# Teste_lad.net
KiCad netlist of a schematic drawn in EAGLE
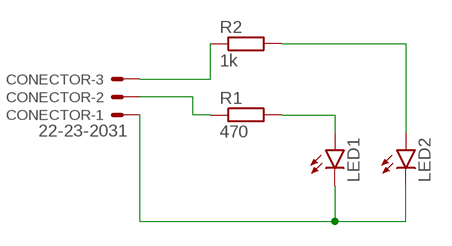
[diagram p0: schematic, sheet 1]

(export (version "E")
  (design (tool "Eeschema 10.0.6"))
  (components
    (comp (ref "CONECTOR")
      (value "22-23-2031")
      (footprint "eagle-import:22-23-2031")
      (fields (field (name "MF") "MOLEX"))
      (libsource (lib "eagle-import") (part "22-23-2031"))
    )
    (comp (ref "LED1")
      (value "LED5MM")
      (footprint "eagle-import:LED5MM")
      (libsource (lib "eagle-import") (part "LED5MM"))
    )
    (comp (ref "LED2")
      (value "LED5MM")
      (footprint "eagle-import:LED5MM")
      (libsource (lib "eagle-import") (part "LED5MM"))
    )
    (comp (ref "R1")
      (value "470")
      (footprint "eagle-import:0204_7")
      (libsource (lib "eagle-import") (part "R-EU_0204/7"))
    )
    (comp (ref "R2")
      (value "1k")
      (footprint "eagle-import:0204_7")
      (libsource (lib "eagle-import") (part "R-EU_0204/7"))
    )
  )
  (nets
    (net (code "1") (name "Net-(CONECTORA-S)") (class "Default")
      (node (ref "CONECTOR") (pin "1") (pinfunction "S_1") (pintype "passive"))
      (node (ref "LED1") (pin "K") (pinfunction "C_K") (pintype "passive"))
      (node (ref "LED2") (pin "K") (pinfunction "C_K") (pintype "passive"))
    )
    (net (code "2") (name "Net-(CONECTORB-S)") (class "Default")
      (node (ref "CONECTOR") (pin "2") (pinfunction "S_2") (pintype "passive"))
      (node (ref "R1") (pin "1") (pinfunction "1_1") (pintype "passive"))
    )
    (net (code "3") (name "Net-(CONECTORC-S)") (class "Default")
      (node (ref "CONECTOR") (pin "3") (pinfunction "S_3") (pintype "passive"))
      (node (ref "R2") (pin "1") (pinfunction "1_1") (pintype "passive"))
    )
    (net (code "4") (name "Net-(LED1-PadA)") (class "Default")
      (node (ref "LED1") (pin "A") (pinfunction "A_A") (pintype "passive"))
      (node (ref "R1") (pin "2") (pinfunction "2_2") (pintype "passive"))
    )
    (net (code "5") (name "Net-(LED2-PadA)") (class "Default")
      (node (ref "LED2") (pin "A") (pinfunction "A_A") (pintype "passive"))
      (node (ref "R2") (pin "2") (pinfunction "2_2") (pintype "passive"))
    )
  )
)
